# main.net
KiCad netlist of a schematic drawn in Altium Designer
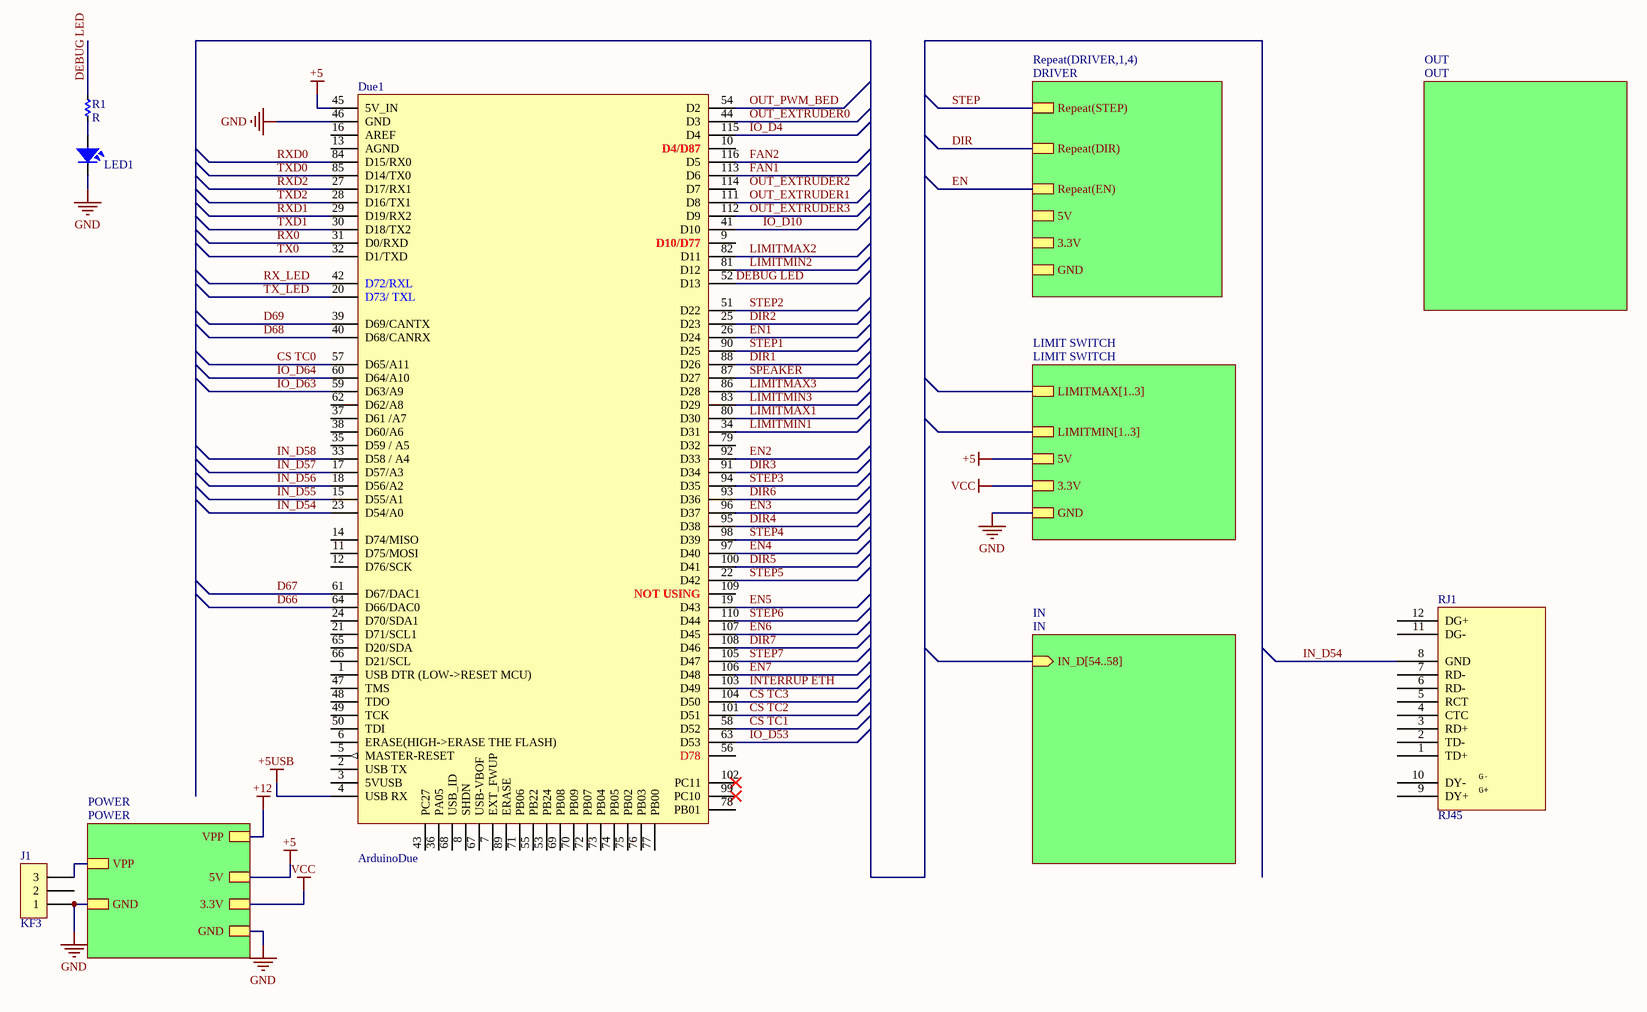
[diagram p0: main.SchDoc]

(export (version "E")
  (design (tool "Eeschema 10.0.6"))
  (components
    (comp (ref "Due1")
      (value "ArduinoDue")
      (footprint "DUE_MODULE")
      (libsource (lib "nhan") (part "ArduinoDue"))
    )
    (comp (ref "J1")
      (value "KF3")
      (footprint "KF3-5.08T")
      (fields
        (field (name "MANUFACTURER") "Würth Elektronik eiSos GmbH")
        (field (name "PARTNO") "691103110003")
        (field (name "CREATED BY") "Karrer Zheng")
      )
      (libsource (lib "BanLinhKien") (part "KF3"))
    )
    (comp (ref "LED1") (value "LED") (footprint "LED-0805-Blue") (libsource (lib "LIBRARY") (part "LED SMD")))
    (comp (ref "R1") (value "R") (footprint "RES-SMD-0603_BIG") (libsource (lib "nhan") (part "R")))
    (comp (ref "RJ1") (value "RJ45") (footprint "RJ45-Dung") (libsource (lib "nhan") (part "CON JR45")))
  )
  (nets
    (net (code "1") (name "+5") (class "Default")
      (node (ref "Due1") (pin "45") (pinfunction "5V_IN_45") (pintype "passive"))
    )
    (net (code "2") (name "+5USB") (class "Default")
      (node (ref "Due1") (pin "4") (pinfunction "USB_RX_4") (pintype "passive"))
    )
    (net (code "6") (name "/CS TC0") (class "Default")
      (node (ref "Due1") (pin "57") (pinfunction "D65/A11_57") (pintype "passive"))
    )
    (net (code "7") (name "/CS TC1") (class "Default")
      (node (ref "Due1") (pin "58") (pinfunction "D52_58") (pintype "passive"))
    )
    (net (code "8") (name "/CS TC2") (class "Default")
      (node (ref "Due1") (pin "101") (pinfunction "D51_101") (pintype "passive"))
    )
    (net (code "9") (name "/CS TC3") (class "Default")
      (node (ref "Due1") (pin "104") (pinfunction "D50_104") (pintype "passive"))
    )
    (net (code "10") (name "/D66") (class "Default")
      (node (ref "Due1") (pin "64") (pinfunction "D66/DAC0_64") (pintype "passive"))
    )
    (net (code "11") (name "/D67") (class "Default")
      (node (ref "Due1") (pin "61") (pinfunction "D67/DAC1_61") (pintype "passive"))
    )
    (net (code "12") (name "/D68") (class "Default")
      (node (ref "Due1") (pin "40") (pinfunction "D68/CANRX_40") (pintype "passive"))
    )
    (net (code "13") (name "/D69") (class "Default")
      (node (ref "Due1") (pin "39") (pinfunction "D69/CANTX_39") (pintype "passive"))
    )
    (net (code "14") (name "/DEBUG LED") (class "Default")
      (node (ref "Due1") (pin "52") (pinfunction "D13_52") (pintype "passive"))
      (node (ref "R1") (pin "1") (pinfunction "1_1") (pintype "passive"))
    )
    (net (code "16") (name "/DIR1") (class "Default")
      (node (ref "Due1") (pin "88") (pinfunction "D26_88") (pintype "passive"))
    )
    (net (code "17") (name "/DIR2") (class "Default")
      (node (ref "Due1") (pin "25") (pinfunction "D23_25") (pintype "passive"))
    )
    (net (code "18") (name "/DIR3") (class "Default")
      (node (ref "Due1") (pin "91") (pinfunction "D34_91") (pintype "passive"))
    )
    (net (code "19") (name "/DIR4") (class "Default")
      (node (ref "Due1") (pin "95") (pinfunction "D38_95") (pintype "passive"))
    )
    (net (code "20") (name "/DIR5") (class "Default")
      (node (ref "Due1") (pin "100") (pinfunction "D41_100") (pintype "passive"))
    )
    (net (code "21") (name "/DIR6") (class "Default")
      (node (ref "Due1") (pin "93") (pinfunction "D36_93") (pintype "passive"))
    )
    (net (code "22") (name "/DIR7") (class "Default")
      (node (ref "Due1") (pin "108") (pinfunction "D46_108") (pintype "passive"))
    )
    (net (code "24") (name "/EN1") (class "Default")
      (node (ref "Due1") (pin "26") (pinfunction "D24_26") (pintype "passive"))
    )
    (net (code "25") (name "/EN2") (class "Default")
      (node (ref "Due1") (pin "92") (pinfunction "D33_92") (pintype "passive"))
    )
    (net (code "26") (name "/EN3") (class "Default")
      (node (ref "Due1") (pin "96") (pinfunction "D37_96") (pintype "passive"))
    )
    (net (code "27") (name "/EN4") (class "Default")
      (node (ref "Due1") (pin "97") (pinfunction "D40_97") (pintype "passive"))
    )
    (net (code "28") (name "/EN5") (class "Default")
      (node (ref "Due1") (pin "19") (pinfunction "D43_19") (pintype "passive"))
    )
    (net (code "29") (name "/EN6") (class "Default")
      (node (ref "Due1") (pin "107") (pinfunction "D45_107") (pintype "passive"))
    )
    (net (code "30") (name "/EN7") (class "Default")
      (node (ref "Due1") (pin "106") (pinfunction "D48_106") (pintype "passive"))
    )
    (net (code "31") (name "/FAN1") (class "Default")
      (node (ref "Due1") (pin "113") (pinfunction "D6_113") (pintype "passive"))
    )
    (net (code "32") (name "/FAN2") (class "Default")
      (node (ref "Due1") (pin "116") (pinfunction "D5_116") (pintype "passive"))
    )
    (net (code "34") (name "/INTERRUP ETH") (class "Default")
      (node (ref "Due1") (pin "103") (pinfunction "D49_103") (pintype "passive"))
    )
    (net (code "35") (name "/IN_D54") (class "Default")
      (node (ref "Due1") (pin "23") (pinfunction "D54/A0_23") (pintype "passive"))
      (node (ref "RJ1") (pin "8") (pinfunction "GND_8") (pintype "power_in"))
    )
    (net (code "36") (name "/IN_D55") (class "Default")
      (node (ref "Due1") (pin "15") (pinfunction "D55/A1_15") (pintype "passive"))
    )
    (net (code "37") (name "/IN_D56") (class "Default")
      (node (ref "Due1") (pin "18") (pinfunction "D56/A2_18") (pintype "passive"))
    )
    (net (code "38") (name "/IN_D57") (class "Default")
      (node (ref "Due1") (pin "17") (pinfunction "D57/A3_17") (pintype "passive"))
    )
    (net (code "39") (name "/IN_D58") (class "Default")
      (node (ref "Due1") (pin "33") (pinfunction "D58_/_A4_33") (pintype "passive"))
    )
    (net (code "41") (name "/IO_D4") (class "Default")
      (node (ref "Due1") (pin "115") (pinfunction "D4_115") (pintype "passive"))
    )
    (net (code "42") (name "/IO_D10") (class "Default")
      (node (ref "Due1") (pin "41") (pinfunction "D10_41") (pintype "passive"))
    )
    (net (code "43") (name "/IO_D53") (class "Default")
      (node (ref "Due1") (pin "63") (pinfunction "D53_63") (pintype "passive"))
    )
    (net (code "44") (name "/IO_D63") (class "Default")
      (node (ref "Due1") (pin "59") (pinfunction "D63/A9_59") (pintype "passive"))
    )
    (net (code "45") (name "/IO_D64") (class "Default")
      (node (ref "Due1") (pin "60") (pinfunction "D64/A10_60") (pintype "passive"))
    )
    (net (code "46") (name "/LIMITMAX1") (class "Default")
      (node (ref "Due1") (pin "80") (pinfunction "D30_80") (pintype "passive"))
    )
    (net (code "47") (name "/LIMITMAX2") (class "Default")
      (node (ref "Due1") (pin "82") (pinfunction "D11_82") (pintype "passive"))
    )
    (net (code "48") (name "/LIMITMAX3") (class "Default")
      (node (ref "Due1") (pin "86") (pinfunction "D28_86") (pintype "passive"))
    )
    (net (code "50") (name "/LIMITMIN1") (class "Default")
      (node (ref "Due1") (pin "34") (pinfunction "D31_34") (pintype "passive"))
    )
    (net (code "51") (name "/LIMITMIN2") (class "Default")
      (node (ref "Due1") (pin "81") (pinfunction "D12_81") (pintype "passive"))
    )
    (net (code "52") (name "/LIMITMIN3") (class "Default")
      (node (ref "Due1") (pin "83") (pinfunction "D29_83") (pintype "passive"))
    )
    (net (code "54") (name "/OUT_EXTRUDER0") (class "Default")
      (node (ref "Due1") (pin "44") (pinfunction "D3_44") (pintype "passive"))
    )
    (net (code "55") (name "/OUT_EXTRUDER1") (class "Default")
      (node (ref "Due1") (pin "111") (pinfunction "D8_111") (pintype "passive"))
    )
    (net (code "57") (name "/OUT_EXTRUDER3") (class "Default")
      (node (ref "Due1") (pin "112") (pinfunction "D9_112") (pintype "passive"))
    )
    (net (code "58") (name "/OUT_PWM_BED") (class "Default")
      (node (ref "Due1") (pin "54") (pinfunction "D2_54") (pintype "passive"))
    )
    (net (code "59") (name "/RX0") (class "Default")
      (node (ref "Due1") (pin "31") (pinfunction "D0/RXD_31") (pintype "passive"))
    )
    (net (code "60") (name "/RXD0") (class "Default")
      (node (ref "Due1") (pin "84") (pinfunction "D15/RX0_84") (pintype "passive"))
    )
    (net (code "61") (name "/RXD1") (class "Default")
      (node (ref "Due1") (pin "29") (pinfunction "D19/RX2_29") (pintype "passive"))
    )
    (net (code "62") (name "/RXD2") (class "Default")
      (node (ref "Due1") (pin "27") (pinfunction "D17/RX1_27") (pintype "passive"))
    )
    (net (code "63") (name "/RX_LED") (class "Default")
      (node (ref "Due1") (pin "42") (pinfunction "D72/RXL_42") (pintype "passive"))
    )
    (net (code "64") (name "/SPEAKER") (class "Default")
      (node (ref "Due1") (pin "87") (pinfunction "D27_87") (pintype "passive"))
    )
    (net (code "66") (name "/STEP1") (class "Default")
      (node (ref "Due1") (pin "90") (pinfunction "D25_90") (pintype "passive"))
    )
    (net (code "67") (name "/STEP2") (class "Default")
      (node (ref "Due1") (pin "51") (pinfunction "D22_51") (pintype "passive"))
    )
    (net (code "68") (name "/STEP3") (class "Default")
      (node (ref "Due1") (pin "94") (pinfunction "D35_94") (pintype "passive"))
    )
    (net (code "69") (name "/STEP4") (class "Default")
      (node (ref "Due1") (pin "98") (pinfunction "D39_98") (pintype "passive"))
    )
    (net (code "70") (name "/STEP5") (class "Default")
      (node (ref "Due1") (pin "22") (pinfunction "D42_22") (pintype "passive"))
    )
    (net (code "71") (name "/STEP6") (class "Default")
      (node (ref "Due1") (pin "110") (pinfunction "D44_110") (pintype "passive"))
    )
    (net (code "72") (name "/STEP7") (class "Default")
      (node (ref "Due1") (pin "105") (pinfunction "D47_105") (pintype "passive"))
    )
    (net (code "73") (name "/TX0") (class "Default")
      (node (ref "Due1") (pin "32") (pinfunction "D1/TXD_32") (pintype "passive"))
    )
    (net (code "74") (name "/TXD0") (class "Default")
      (node (ref "Due1") (pin "85") (pinfunction "D14/TX0_85") (pintype "passive"))
    )
    (net (code "75") (name "/TXD1") (class "Default")
      (node (ref "Due1") (pin "30") (pinfunction "D18/TX2_30") (pintype "passive"))
    )
    (net (code "76") (name "/TXD2") (class "Default")
      (node (ref "Due1") (pin "28") (pinfunction "D16/TX1_28") (pintype "passive"))
    )
    (net (code "77") (name "/TX_LED") (class "Default")
      (node (ref "Due1") (pin "20") (pinfunction "D73/_TXL_20") (pintype "passive"))
    )
    (net (code "78") (name "/VPP") (class "Default")
      (node (ref "J1") (pin "3") (pinfunction "3_3") (pintype "passive"))
    )
    (net (code "79") (name "GND") (class "Default")
      (node (ref "Due1") (pin "46") (pinfunction "GND_46") (pintype "passive"))
      (node (ref "J1") (pin "1") (pinfunction "1_1") (pintype "passive"))
      (node (ref "LED1") (pin "2") (pinfunction "2_2") (pintype "passive"))
    )
    (net (code "80") (name "Net-(LED1-Pad1)") (class "Default")
      (node (ref "LED1") (pin "1") (pinfunction "1_1") (pintype "passive"))
      (node (ref "R1") (pin "2") (pinfunction "2_2") (pintype "passive"))
    )
    (net (code "82") (name "unconnected-(Due1-5VUSB-Pad3)") (class "Default")
      (node (ref "Due1") (pin "3") (pinfunction "5VUSB_3") (pintype "passive"))
    )
    (net (code "83") (name "unconnected-(Due1-AGND-Pad13)") (class "Default")
      (node (ref "Due1") (pin "13") (pinfunction "AGND_13") (pintype "passive"))
    )
    (net (code "84") (name "unconnected-(Due1-AREF-Pad16)") (class "Default")
      (node (ref "Due1") (pin "16") (pinfunction "AREF_16") (pintype "passive"))
    )
    (net (code "85") (name "unconnected-(Due1-D4{slash}D87-Pad10)") (class "Default")
      (node (ref "Due1") (pin "10") (pinfunction "D4/D87_10") (pintype "passive"))
    )
    (net (code "86") (name "unconnected-(Due1-D7-Pad114)") (class "Default")
      (node (ref "Due1") (pin "114") (pinfunction "D7_114") (pintype "passive"))
    )
    (net (code "87") (name "unconnected-(Due1-D10{slash}D77-Pad9)") (class "Default")
      (node (ref "Due1") (pin "9") (pinfunction "D10/D77_9") (pintype "passive"))
    )
    (net (code "88") (name "unconnected-(Due1-D20{slash}SDA-Pad65)") (class "Default")
      (node (ref "Due1") (pin "65") (pinfunction "D20/SDA_65") (pintype "passive"))
    )
    (net (code "89") (name "unconnected-(Due1-D21{slash}SCL-Pad66)") (class "Default")
      (node (ref "Due1") (pin "66") (pinfunction "D21/SCL_66") (pintype "passive"))
    )
    (net (code "90") (name "unconnected-(Due1-D32-Pad79)") (class "Default")
      (node (ref "Due1") (pin "79") (pinfunction "D32_79") (pintype "passive"))
    )
    (net (code "91") (name "unconnected-(Due1-D59_{slash}_A5-Pad35)") (class "Default")
      (node (ref "Due1") (pin "35") (pinfunction "D59_/_A5_35") (pintype "passive"))
    )
    (net (code "92") (name "unconnected-(Due1-D60{slash}A6-Pad38)") (class "Default")
      (node (ref "Due1") (pin "38") (pinfunction "D60/A6_38") (pintype "passive"))
    )
    (net (code "93") (name "unconnected-(Due1-D61_{slash}A7-Pad37)") (class "Default")
      (node (ref "Due1") (pin "37") (pinfunction "D61_/A7_37") (pintype "passive"))
    )
    (net (code "94") (name "unconnected-(Due1-D62{slash}A8-Pad62)") (class "Default")
      (node (ref "Due1") (pin "62") (pinfunction "D62/A8_62") (pintype "passive"))
    )
    (net (code "95") (name "unconnected-(Due1-D70{slash}SDA1-Pad24)") (class "Default")
      (node (ref "Due1") (pin "24") (pinfunction "D70/SDA1_24") (pintype "passive"))
    )
    (net (code "96") (name "unconnected-(Due1-D71{slash}SCL1-Pad21)") (class "Default")
      (node (ref "Due1") (pin "21") (pinfunction "D71/SCL1_21") (pintype "passive"))
    )
    (net (code "97") (name "unconnected-(Due1-D74{slash}MISO-Pad14)") (class "Default")
      (node (ref "Due1") (pin "14") (pinfunction "D74/MISO_14") (pintype "passive"))
    )
    (net (code "98") (name "unconnected-(Due1-D75{slash}MOSI-Pad11)") (class "Default")
      (node (ref "Due1") (pin "11") (pinfunction "D75/MOSI_11") (pintype "passive"))
    )
    (net (code "99") (name "unconnected-(Due1-D76{slash}SCK-Pad12)") (class "Default")
      (node (ref "Due1") (pin "12") (pinfunction "D76/SCK_12") (pintype "passive"))
    )
    (net (code "100") (name "unconnected-(Due1-D78-Pad56)") (class "Default")
      (node (ref "Due1") (pin "56") (pinfunction "D78_56") (pintype "passive"))
    )
    (net (code "101") (name "unconnected-(Due1-ERASE(HIGH->ERASE_THE_FLASH)-Pad6)") (class "Default")
      (node (ref "Due1") (pin "6") (pinfunction "ERASE(HIGH->ERASE_THE_FLASH)_6") (pintype "passive"))
    )
    (net (code "102") (name "unconnected-(Due1-ERASE-Pad89)") (class "Default")
      (node (ref "Due1") (pin "89") (pinfunction "ERASE_89") (pintype "passive"))
    )
    (net (code "103") (name "unconnected-(Due1-EXT_FWUP-Pad7)") (class "Default")
      (node (ref "Due1") (pin "7") (pinfunction "EXT_FWUP_7") (pintype "passive"))
    )
    (net (code "104") (name "unconnected-(Due1-MASTER-RESET-Pad5)") (class "Default")
      (node (ref "Due1") (pin "5") (pinfunction "MASTER-RESET_5") (pintype "output"))
    )
    (net (code "105") (name "unconnected-(Due1-NOT_USING-Pad109)") (class "Default")
      (node (ref "Due1") (pin "109") (pinfunction "NOT_USING_109") (pintype "passive"))
    )
    (net (code "106") (name "unconnected-(Due1-PA05-Pad36)") (class "Default")
      (node (ref "Due1") (pin "36") (pinfunction "PA05_36") (pintype "passive"))
    )
    (net (code "107") (name "unconnected-(Due1-PB00-Pad77)") (class "Default")
      (node (ref "Due1") (pin "77") (pinfunction "PB00_77") (pintype "passive"))
    )
    (net (code "108") (name "unconnected-(Due1-PB01-Pad78)") (class "Default")
      (node (ref "Due1") (pin "78") (pinfunction "PB01_78") (pintype "passive"))
    )
    (net (code "109") (name "unconnected-(Due1-PB02-Pad75)") (class "Default")
      (node (ref "Due1") (pin "75") (pinfunction "PB02_75") (pintype "passive"))
    )
    (net (code "110") (name "unconnected-(Due1-PB03-Pad76)") (class "Default")
      (node (ref "Due1") (pin "76") (pinfunction "PB03_76") (pintype "passive"))
    )
    (net (code "111") (name "unconnected-(Due1-PB04-Pad73)") (class "Default")
      (node (ref "Due1") (pin "73") (pinfunction "PB04_73") (pintype "passive"))
    )
    (net (code "112") (name "unconnected-(Due1-PB05-Pad74)") (class "Default")
      (node (ref "Due1") (pin "74") (pinfunction "PB05_74") (pintype "passive"))
    )
    (net (code "113") (name "unconnected-(Due1-PB06-Pad71)") (class "Default")
      (node (ref "Due1") (pin "71") (pinfunction "PB06_71") (pintype "passive"))
    )
    (net (code "114") (name "unconnected-(Due1-PB07-Pad72)") (class "Default")
      (node (ref "Due1") (pin "72") (pinfunction "PB07_72") (pintype "passive"))
    )
    (net (code "115") (name "unconnected-(Due1-PB08-Pad69)") (class "Default")
      (node (ref "Due1") (pin "69") (pinfunction "PB08_69") (pintype "passive"))
    )
    (net (code "116") (name "unconnected-(Due1-PB09-Pad70)") (class "Default")
      (node (ref "Due1") (pin "70") (pinfunction "PB09_70") (pintype "passive"))
    )
    (net (code "117") (name "unconnected-(Due1-PB22-Pad55)") (class "Default")
      (node (ref "Due1") (pin "55") (pinfunction "PB22_55") (pintype "passive"))
    )
    (net (code "118") (name "unconnected-(Due1-PB24-Pad53)") (class "Default")
      (node (ref "Due1") (pin "53") (pinfunction "PB24_53") (pintype "passive"))
    )
    (net (code "119") (name "unconnected-(Due1-PC10-Pad99)") (class "Default")
      (node (ref "Due1") (pin "99") (pinfunction "PC10_99") (pintype "passive+no_connect"))
    )
    (net (code "120") (name "unconnected-(Due1-PC11-Pad102)") (class "Default")
      (node (ref "Due1") (pin "102") (pinfunction "PC11_102") (pintype "passive+no_connect"))
    )
    (net (code "121") (name "unconnected-(Due1-PC27-Pad43)") (class "Default")
      (node (ref "Due1") (pin "43") (pinfunction "PC27_43") (pintype "passive"))
    )
    (net (code "122") (name "unconnected-(Due1-SHDN-Pad8)") (class "Default")
      (node (ref "Due1") (pin "8") (pinfunction "SHDN_8") (pintype "passive"))
    )
    (net (code "123") (name "unconnected-(Due1-TCK-Pad49)") (class "Default")
      (node (ref "Due1") (pin "49") (pinfunction "TCK_49") (pintype "passive"))
    )
    (net (code "124") (name "unconnected-(Due1-TDI-Pad50)") (class "Default")
      (node (ref "Due1") (pin "50") (pinfunction "TDI_50") (pintype "passive"))
    )
    (net (code "125") (name "unconnected-(Due1-TDO-Pad48)") (class "Default")
      (node (ref "Due1") (pin "48") (pinfunction "TDO_48") (pintype "passive"))
    )
    (net (code "126") (name "unconnected-(Due1-TMS-Pad47)") (class "Default")
      (node (ref "Due1") (pin "47") (pinfunction "TMS_47") (pintype "passive"))
    )
    (net (code "127") (name "unconnected-(Due1-USB-VBOF-Pad67)") (class "Default")
      (node (ref "Due1") (pin "67") (pinfunction "USB-VBOF_67") (pintype "passive"))
    )
    (net (code "128") (name "unconnected-(Due1-USB_DTR_(LOW->RESET_MCU)-Pad1)") (class "Default")
      (node (ref "Due1") (pin "1") (pinfunction "USB_DTR_(LOW->RESET_MCU)_1") (pintype "passive"))
    )
    (net (code "129") (name "unconnected-(Due1-USB_ID-Pad68)") (class "Default")
      (node (ref "Due1") (pin "68") (pinfunction "USB_ID_68") (pintype "passive"))
    )
    (net (code "130") (name "unconnected-(Due1-USB_TX-Pad2)") (class "Default")
      (node (ref "Due1") (pin "2") (pinfunction "USB_TX_2") (pintype "passive"))
    )
    (net (code "131") (name "unconnected-(J1-Pad2)") (class "Default")
      (node (ref "J1") (pin "2") (pinfunction "2_2") (pintype "passive"))
    )
    (net (code "132") (name "unconnected-(RJ1-CTC-Pad4)") (class "Default")
      (node (ref "RJ1") (pin "4") (pinfunction "CTC_4") (pintype "passive"))
    )
    (net (code "133") (name "unconnected-(RJ1-DG+-Pad12)") (class "Default")
      (node (ref "RJ1") (pin "12") (pinfunction "DG+_12") (pintype "passive"))
    )
    (net (code "134") (name "unconnected-(RJ1-DG--Pad11)") (class "Default")
      (node (ref "RJ1") (pin "11") (pinfunction "DG-_11") (pintype "passive"))
    )
    (net (code "135") (name "unconnected-(RJ1-DY+-Pad9)") (class "Default")
      (node (ref "RJ1") (pin "9") (pinfunction "DY+_9") (pintype "passive"))
    )
    (net (code "136") (name "unconnected-(RJ1-DY--Pad10)") (class "Default")
      (node (ref "RJ1") (pin "10") (pinfunction "DY-_10") (pintype "passive"))
    )
    (net (code "137") (name "unconnected-(RJ1-RCT-Pad5)") (class "Default")
      (node (ref "RJ1") (pin "5") (pinfunction "RCT_5") (pintype "passive"))
    )
    (net (code "138") (name "unconnected-(RJ1-RD+-Pad3)") (class "Default")
      (node (ref "RJ1") (pin "3") (pinfunction "RD+_3") (pintype "passive"))
    )
    (net (code "139") (name "unconnected-(RJ1-RD--Pad6)") (class "Default")
      (node (ref "RJ1") (pin "6") (pinfunction "RD-_6") (pintype "passive"))
    )
    (net (code "140") (name "unconnected-(RJ1-RD--Pad7)") (class "Default")
      (node (ref "RJ1") (pin "7") (pinfunction "RD-_7") (pintype "passive"))
    )
    (net (code "141") (name "unconnected-(RJ1-TD+-Pad1)") (class "Default")
      (node (ref "RJ1") (pin "1") (pinfunction "TD+_1") (pintype "passive"))
    )
    (net (code "142") (name "unconnected-(RJ1-TD--Pad2)") (class "Default")
      (node (ref "RJ1") (pin "2") (pinfunction "TD-_2") (pintype "passive"))
    )
  )
)
